# DRV8874.net
KiCad netlist of a schematic drawn in Altium Designer
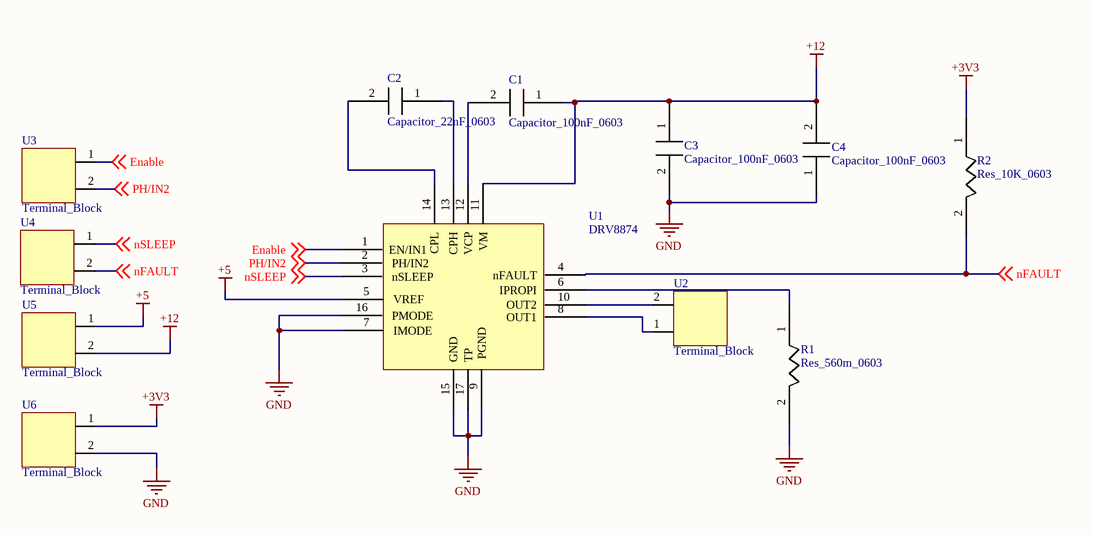
[diagram p0: DRV8874.SchDoc]

(export (version "E")
  (design (tool "Eeschema 10.0.6"))
  (components
    (comp (ref "C1")
      (value "Capacitor_100nF_0603")
      (footprint "Capacitor_0603")
      (libsource (lib "Copy of Integrated_Library1[1]") (part "Capacitor_100nF_0603"))
    )
    (comp (ref "C2")
      (value "Capacitor_22nF_0603")
      (footprint "Capacitor_0603")
      (libsource (lib "Copy of Integrated_Library1[1]") (part "Capacitor_22nF_0603"))
    )
    (comp (ref "C3")
      (value "Capacitor_100nF_0603")
      (footprint "Capacitor_0603")
      (libsource (lib "Copy of Integrated_Library1[1]") (part "Capacitor_100nF_0603"))
    )
    (comp (ref "C4")
      (value "Capacitor_100nF_0603")
      (footprint "Capacitor_0603")
      (libsource (lib "Copy of Integrated_Library1[1]") (part "Capacitor_100nF_0603"))
    )
    (comp (ref "R1")
      (value "Res_560m_0603")
      (footprint "Res_10K_0603")
      (libsource (lib "Copy of Integrated_Library1[1]") (part "Res_560m_0603"))
    )
    (comp (ref "R2")
      (value "Res_10K_0603")
      (footprint "Res_10K_0603")
      (libsource (lib "Copy of Integrated_Library1[1]") (part "Res_10K_0603"))
    )
    (comp (ref "U1")
      (value "DRV8874")
      (footprint "DRV8874")
      (fields (field (name "MANUFACTURER") "Texas instruments"))
      (libsource (lib "Copy of Integrated_Library1[1]") (part "DRV8874"))
    )
    (comp (ref "U2")
      (value "Terminal_Block")
      (footprint "Terminal_Block")
      (libsource (lib "") (part "Terminal_Block_1"))
    )
    (comp (ref "U3")
      (value "Terminal_Block")
      (footprint "Terminal_Block")
      (libsource (lib "Copy of Integrated_Library1[1]") (part "Terminal_Block"))
    )
    (comp (ref "U4")
      (value "Terminal_Block")
      (footprint "Terminal_Block")
      (libsource (lib "Copy of Integrated_Library1[1]") (part "Terminal_Block"))
    )
    (comp (ref "U5")
      (value "Terminal_Block")
      (footprint "Terminal_Block")
      (libsource (lib "Copy of Integrated_Library1[1]") (part "Terminal_Block"))
    )
    (comp (ref "U6")
      (value "Terminal_Block")
      (footprint "Terminal_Block")
      (libsource (lib "Copy of Integrated_Library1[1]") (part "Terminal_Block"))
    )
  )
  (nets
    (net (code "1") (name "+3V3") (class "Default")
      (node (ref "R2") (pin "1") (pintype "passive"))
      (node (ref "U6") (pin "1") (pintype "passive"))
    )
    (net (code "2") (name "+5") (class "Default")
      (node (ref "U1") (pin "5") (pinfunction "_VREF_5") (pintype "passive"))
      (node (ref "U5") (pin "1") (pintype "passive"))
    )
    (net (code "3") (name "+12") (class "Default")
      (node (ref "C1") (pin "1") (pintype "passive"))
      (node (ref "C3") (pin "1") (pintype "passive"))
      (node (ref "C4") (pin "2") (pintype "passive"))
      (node (ref "U1") (pin "11") (pinfunction "_VM_11") (pintype "passive"))
      (node (ref "U5") (pin "2") (pintype "passive"))
    )
    (net (code "4") (name "Enable") (class "Default")
      (node (ref "U1") (pin "1") (pinfunction "EN/IN1_1") (pintype "passive"))
      (node (ref "U3") (pin "1") (pintype "passive"))
    )
    (net (code "5") (name "GND") (class "Default")
      (node (ref "C3") (pin "2") (pintype "passive"))
      (node (ref "C4") (pin "1") (pintype "passive"))
      (node (ref "R1") (pin "2") (pintype "passive"))
      (node (ref "U1") (pin "15") (pinfunction "GND_15") (pintype "passive"))
      (node (ref "U1") (pin "16") (pinfunction "_PMODE_16") (pintype "passive"))
      (node (ref "U1") (pin "17") (pinfunction "TP_17") (pintype "passive"))
      (node (ref "U1") (pin "7") (pinfunction "_IMODE_7") (pintype "passive"))
      (node (ref "U1") (pin "9") (pinfunction "_PGND_9") (pintype "passive"))
      (node (ref "U6") (pin "2") (pintype "passive"))
    )
    (net (code "6") (name "Net-(U1-CPH)") (class "Default")
      (node (ref "C2") (pin "1") (pintype "passive"))
      (node (ref "U1") (pin "13") (pinfunction "CPH_13") (pintype "passive"))
    )
    (net (code "7") (name "Net-(U1-OUT2)") (class "Default")
      (node (ref "U1") (pin "10") (pinfunction "OUT2_10") (pintype "passive"))
      (node (ref "U2") (pin "2") (pintype "passive"))
    )
    (net (code "8") (name "Net-(U1-VCP)") (class "Default")
      (node (ref "C1") (pin "2") (pintype "passive"))
      (node (ref "U1") (pin "12") (pinfunction "VCP_12") (pintype "passive"))
    )
    (net (code "9") (name "Net-(U1-_CPL)") (class "Default")
      (node (ref "C2") (pin "2") (pintype "passive"))
      (node (ref "U1") (pin "14") (pinfunction "_CPL_14") (pintype "passive"))
    )
    (net (code "10") (name "Net-(U1-_IPROPI)") (class "Default")
      (node (ref "R1") (pin "1") (pintype "passive"))
      (node (ref "U1") (pin "6") (pinfunction "_IPROPI_6") (pintype "passive"))
    )
    (net (code "11") (name "Net-(U1-_OUT1)") (class "Default")
      (node (ref "U1") (pin "8") (pinfunction "_OUT1_8") (pintype "passive"))
      (node (ref "U2") (pin "1") (pintype "passive"))
    )
    (net (code "12") (name "PH{slash}IN2") (class "Default")
      (node (ref "U1") (pin "2") (pinfunction "_PH/IN2_2") (pintype "passive"))
      (node (ref "U3") (pin "2") (pintype "passive"))
    )
    (net (code "13") (name "nFAULT") (class "Default")
      (node (ref "R2") (pin "2") (pintype "passive"))
      (node (ref "U1") (pin "4") (pinfunction "_nFAULT_4") (pintype "passive"))
      (node (ref "U4") (pin "2") (pintype "passive"))
    )
    (net (code "14") (name "nSLEEP") (class "Default")
      (node (ref "U1") (pin "3") (pinfunction "_nSLEEP_3") (pintype "passive"))
      (node (ref "U4") (pin "1") (pintype "passive"))
    )
  )
)
